# L9741.net
KiCad netlist of a schematic drawn in Altium Designer
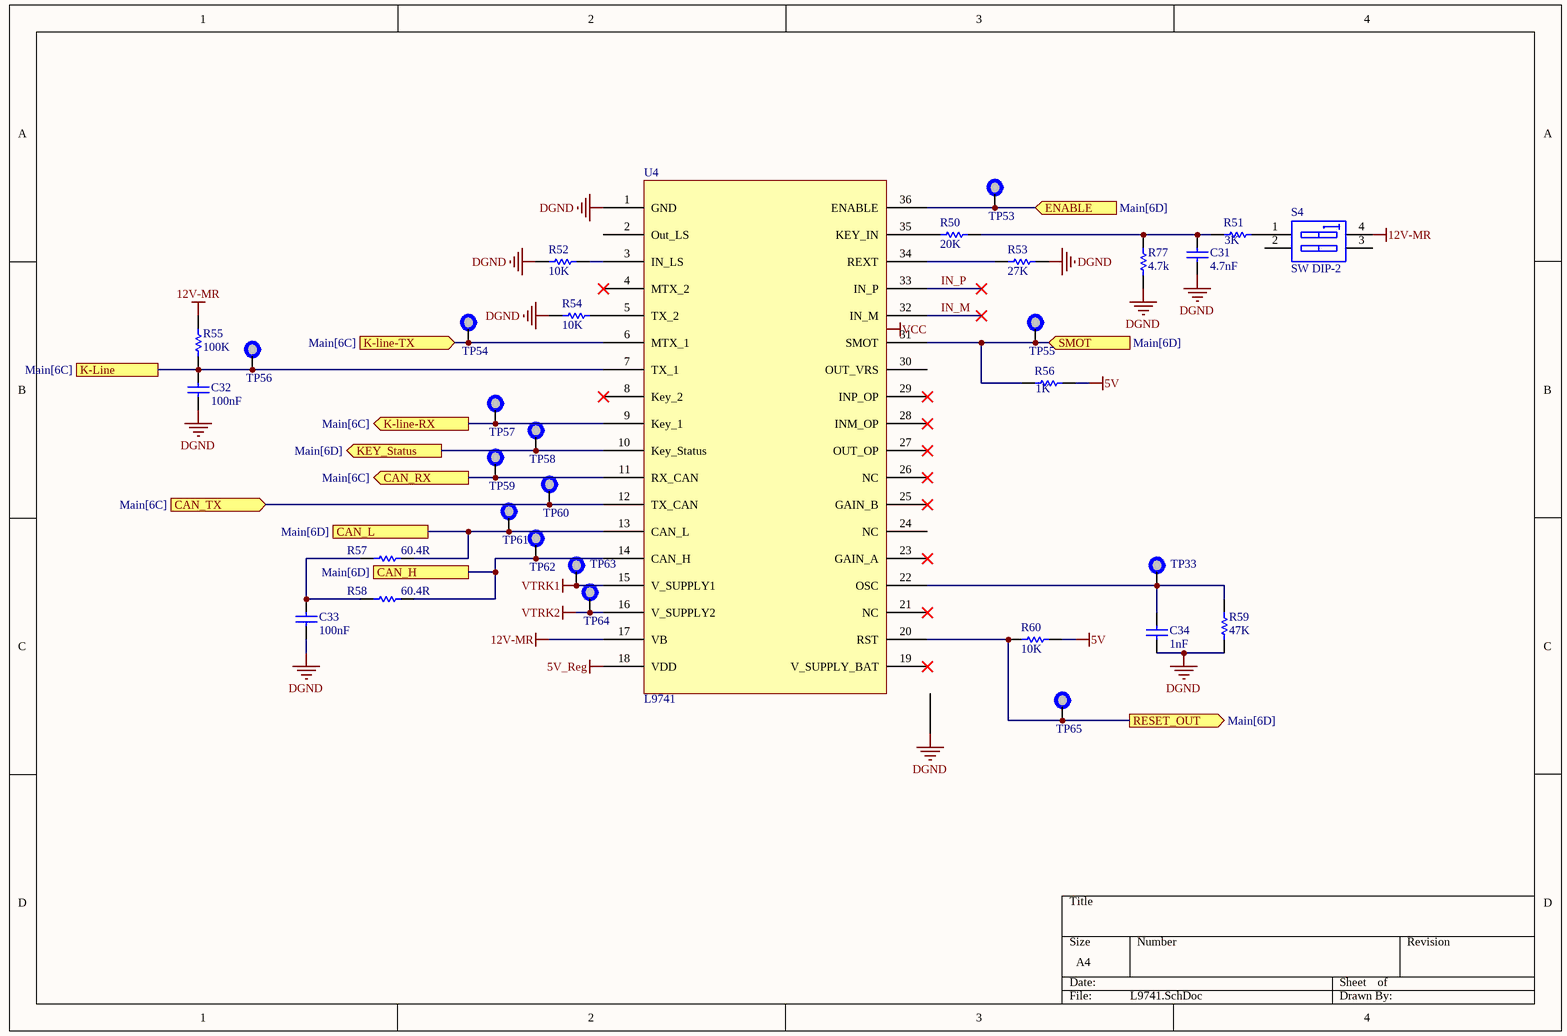
[diagram p0: L9741.SchDoc]

(export (version "E")
  (design (tool "Eeschema 10.0.6"))
  (components
    (comp (ref "C31")
      (value "4.7nF")
      (footprint "0805C")
      (description "LOW ESR")
      (fields (field (name "PUBLISHER") "Altium Limited"))
      (libsource (lib "Miscellaneous Devices") (part "Cap"))
    )
    (comp (ref "C32")
      (value "100nF")
      (footprint "0603c")
      (description "LOW ESR")
      (fields (field (name "PUBLISHER") "Altium Limited"))
      (libsource (lib "Miscellaneous Devices") (part "Cap"))
    )
    (comp (ref "C33")
      (value "100nF")
      (footprint "0603c")
      (description "LOW ESR")
      (fields (field (name "PUBLISHER") "Altium Limited"))
      (libsource (lib "Miscellaneous Devices") (part "Cap"))
    )
    (comp (ref "C34")
      (value "1nF")
      (footprint "0805C")
      (description "LOW ESR")
      (fields (field (name "PUBLISHER") "Altium Limited"))
      (libsource (lib "Miscellaneous Devices") (part "Cap"))
    )
    (comp (ref "R50")
      (value "20K")
      (footprint "0805")
      (description "Resistor")
      (fields (field (name "PUBLISHER") "Altium Limited"))
      (libsource (lib "Miscellaneous Devices") (part "Res1"))
    )
    (comp (ref "R51")
      (value "3K")
      (footprint "0805")
      (description "Resistor")
      (fields (field (name "PUBLISHER") "Altium Limited"))
      (libsource (lib "Miscellaneous Devices") (part "Res1"))
    )
    (comp (ref "R52")
      (value "10K")
      (footprint "0805")
      (description "Resistor")
      (fields (field (name "PUBLISHER") "Altium Limited"))
      (libsource (lib "Miscellaneous Devices") (part "Res1"))
    )
    (comp (ref "R53")
      (value "27K")
      (footprint "0805")
      (description "Resistor")
      (fields (field (name "PUBLISHER") "Altium Limited"))
      (libsource (lib "Miscellaneous Devices") (part "Res1"))
    )
    (comp (ref "R54")
      (value "10K")
      (footprint "0805")
      (description "Resistor")
      (fields (field (name "PUBLISHER") "Altium Limited"))
      (libsource (lib "Miscellaneous Devices") (part "Res1"))
    )
    (comp (ref "R55")
      (value "100K")
      (footprint "0805")
      (description "Resistor")
      (fields (field (name "PUBLISHER") "Altium Limited"))
      (libsource (lib "Miscellaneous Devices") (part "Res1"))
    )
    (comp (ref "R56")
      (value "1K")
      (footprint "0805")
      (description "Resistor")
      (fields (field (name "PUBLISHER") "Altium Limited"))
      (libsource (lib "Miscellaneous Devices") (part "Res1"))
    )
    (comp (ref "R57")
      (value "60.4R")
      (footprint "1206")
      (description "Resistor")
      (fields (field (name "PUBLISHER") "Altium Limited"))
      (libsource (lib "Miscellaneous Devices") (part "Res1"))
    )
    (comp (ref "R58")
      (value "60.4R")
      (footprint "1206")
      (description "Resistor")
      (fields (field (name "PUBLISHER") "Altium Limited"))
      (libsource (lib "Miscellaneous Devices") (part "Res1"))
    )
    (comp (ref "R59")
      (value "47K")
      (footprint "0805")
      (description "Resistor")
      (fields (field (name "PUBLISHER") "Altium Limited"))
      (libsource (lib "Miscellaneous Devices") (part "Res1"))
    )
    (comp (ref "R60")
      (value "10K")
      (footprint "0805")
      (description "Resistor")
      (fields (field (name "PUBLISHER") "Altium Limited"))
      (libsource (lib "Miscellaneous Devices") (part "Res1"))
    )
    (comp (ref "R77")
      (value "4.7k")
      (footprint "0805")
      (description "Resistor")
      (fields (field (name "Comment") "4.7K") (field (name "PUBLISHER") "Altium Limited"))
      (libsource (lib "Miscellaneous Devices") (part "Res1"))
    )
    (comp (ref "S4")
      (value "SW DIP-2")
      (footprint "DIP-4")
      (description "DIP Switch, 2 Position, SPST")
      (fields (field (name "PUBLISHER") "Altium Limited"))
      (libsource (lib "Miscellaneous Devices") (part "SW DIP-2"))
    )
    (comp (ref "TP33") (value "TestPoint") (footprint "TP") (libsource (lib "SchlibV0.1") (part "TestPoint")))
    (comp (ref "TP53") (value "TestPoint") (footprint "TP") (libsource (lib "SchlibV0.1") (part "TestPoint")))
    (comp (ref "TP54") (value "TestPoint") (footprint "TP") (libsource (lib "SchlibV0.1") (part "TestPoint")))
    (comp (ref "TP55") (value "TestPoint") (footprint "TP") (libsource (lib "SchlibV0.1") (part "TestPoint")))
    (comp (ref "TP56") (value "TestPoint") (footprint "TP") (libsource (lib "SchlibV0.1") (part "TestPoint")))
    (comp (ref "TP57") (value "TestPoint") (footprint "TP") (libsource (lib "SchlibV0.1") (part "TestPoint")))
    (comp (ref "TP58") (value "TestPoint") (footprint "TP") (libsource (lib "SchlibV0.1") (part "TestPoint")))
    (comp (ref "TP59") (value "TestPoint") (footprint "TP") (libsource (lib "SchlibV0.1") (part "TestPoint")))
    (comp (ref "TP60") (value "TestPoint") (footprint "TP") (libsource (lib "SchlibV0.1") (part "TestPoint")))
    (comp (ref "TP61") (value "TestPoint") (footprint "TP") (libsource (lib "SchlibV0.1") (part "TestPoint")))
    (comp (ref "TP62") (value "TestPoint") (footprint "TP") (libsource (lib "SchlibV0.1") (part "TestPoint")))
    (comp (ref "TP63") (value "TestPoint") (footprint "TP") (libsource (lib "SchlibV0.1") (part "TestPoint")))
    (comp (ref "TP64") (value "TestPoint") (footprint "TP") (libsource (lib "SchlibV0.1") (part "TestPoint")))
    (comp (ref "TP65") (value "TestPoint") (footprint "TP") (libsource (lib "SchlibV0.1") (part "TestPoint")))
    (comp (ref "U4") (value "L9741") (footprint "L9741") (libsource (lib "SchlibV0.1") (part "L9741")))
  )
  (nets
    (net (code "1") (name "/CAN_H") (class "Default")
      (node (ref "R58") (pin "2") (pinfunction "2_2") (pintype "passive"))
      (node (ref "TP62") (pin "1") (pintype "passive"))
      (node (ref "U4") (pin "14") (pinfunction "CAN_H_14") (pintype "passive"))
    )
    (net (code "2") (name "/CAN_L") (class "Default")
      (node (ref "R57") (pin "2") (pinfunction "2_2") (pintype "passive"))
      (node (ref "TP61") (pin "1") (pintype "passive"))
      (node (ref "U4") (pin "13") (pinfunction "CAN_L_13") (pintype "passive"))
    )
    (net (code "3") (name "/CAN_RX") (class "Default")
      (node (ref "TP59") (pin "1") (pintype "passive"))
      (node (ref "U4") (pin "11") (pinfunction "RX_CAN_11") (pintype "passive"))
    )
    (net (code "4") (name "/CAN_TX") (class "Default")
      (node (ref "TP60") (pin "1") (pintype "passive"))
      (node (ref "U4") (pin "12") (pinfunction "TX_CAN_12") (pintype "passive"))
    )
    (net (code "5") (name "/ENABLE") (class "Default")
      (node (ref "TP53") (pin "1") (pintype "passive"))
      (node (ref "U4") (pin "36") (pinfunction "ENABLE_36") (pintype "passive"))
    )
    (net (code "6") (name "/IN_M") (class "Default")
      (node (ref "U4") (pin "32") (pinfunction "IN_M_32") (pintype "passive+no_connect"))
    )
    (net (code "7") (name "/IN_P") (class "Default")
      (node (ref "U4") (pin "33") (pinfunction "IN_P_33") (pintype "passive+no_connect"))
    )
    (net (code "8") (name "/K-Line") (class "Default")
      (node (ref "C32") (pin "1") (pinfunction "1_1") (pintype "passive"))
      (node (ref "R55") (pin "2") (pinfunction "2_2") (pintype "passive"))
      (node (ref "TP56") (pin "1") (pintype "passive"))
      (node (ref "U4") (pin "7") (pinfunction "TX_1_7") (pintype "passive"))
    )
    (net (code "9") (name "/K-line-RX") (class "Default")
      (node (ref "TP57") (pin "1") (pintype "passive"))
      (node (ref "U4") (pin "9") (pinfunction "Key_1_9") (pintype "passive"))
    )
    (net (code "10") (name "/K-line-TX") (class "Default")
      (node (ref "TP54") (pin "1") (pintype "passive"))
      (node (ref "U4") (pin "6") (pinfunction "MTX_1_6") (pintype "passive"))
    )
    (net (code "11") (name "/KEY_Status") (class "Default")
      (node (ref "TP58") (pin "1") (pintype "passive"))
      (node (ref "U4") (pin "10") (pinfunction "Key_Status_10") (pintype "passive"))
    )
    (net (code "12") (name "/RESET_OUT") (class "Default")
      (node (ref "R60") (pin "2") (pinfunction "2_2") (pintype "passive"))
      (node (ref "TP65") (pin "1") (pintype "passive"))
      (node (ref "U4") (pin "20") (pinfunction "RST_20") (pintype "passive"))
    )
    (net (code "13") (name "/SMOT") (class "Default")
      (node (ref "R56") (pin "1") (pinfunction "1_1") (pintype "passive"))
      (node (ref "TP55") (pin "1") (pintype "passive"))
      (node (ref "U4") (pin "31") (pinfunction "SMOT_31") (pintype "passive"))
    )
    (net (code "14") (name "5V") (class "Default")
      (node (ref "R56") (pin "2") (pinfunction "2_2") (pintype "passive"))
      (node (ref "R60") (pin "1") (pinfunction "1_1") (pintype "passive"))
    )
    (net (code "15") (name "5V_Reg") (class "Default")
      (node (ref "U4") (pin "18") (pinfunction "VDD_18") (pintype "passive"))
    )
    (net (code "16") (name "12V-MR") (class "Default")
      (node (ref "R55") (pin "1") (pinfunction "1_1") (pintype "passive"))
      (node (ref "S4") (pin "4") (pinfunction "B1_4") (pintype "passive"))
      (node (ref "U4") (pin "17") (pinfunction "VB_17") (pintype "passive"))
    )
    (net (code "17") (name "DGND") (class "Default")
      (node (ref "C31") (pin "1") (pinfunction "1_1") (pintype "passive"))
      (node (ref "C32") (pin "2") (pinfunction "2_2") (pintype "passive"))
      (node (ref "C33") (pin "2") (pinfunction "2_2") (pintype "passive"))
      (node (ref "C34") (pin "2") (pinfunction "2_2") (pintype "passive"))
      (node (ref "R52") (pin "2") (pinfunction "2_2") (pintype "passive"))
      (node (ref "R53") (pin "1") (pinfunction "1_1") (pintype "passive"))
      (node (ref "R54") (pin "2") (pinfunction "2_2") (pintype "passive"))
      (node (ref "R59") (pin "2") (pinfunction "2_2") (pintype "passive"))
      (node (ref "R77") (pin "1") (pinfunction "1_1") (pintype "passive"))
      (node (ref "U4") (pin "1") (pinfunction "GND_1") (pintype "passive"))
      (node (ref "U4") (pin "37") (pinfunction "GND_37") (pintype "passive"))
    )
    (net (code "18") (name "Net-(C31-Pad2)") (class "Default")
      (node (ref "C31") (pin "2") (pinfunction "2_2") (pintype "passive"))
      (node (ref "R50") (pin "1") (pinfunction "1_1") (pintype "passive"))
      (node (ref "R51") (pin "1") (pinfunction "1_1") (pintype "passive"))
      (node (ref "R77") (pin "2") (pinfunction "2_2") (pintype "passive"))
    )
    (net (code "19") (name "Net-(C33-Pad1)") (class "Default")
      (node (ref "C33") (pin "1") (pinfunction "1_1") (pintype "passive"))
      (node (ref "R57") (pin "1") (pinfunction "1_1") (pintype "passive"))
      (node (ref "R58") (pin "1") (pinfunction "1_1") (pintype "passive"))
    )
    (net (code "20") (name "Net-(S4-A1)") (class "Default")
      (node (ref "R51") (pin "2") (pinfunction "2_2") (pintype "passive"))
      (node (ref "S4") (pin "1") (pinfunction "A1_1") (pintype "passive"))
    )
    (net (code "21") (name "Net-(U4-IN_LS)") (class "Default")
      (node (ref "R52") (pin "1") (pinfunction "1_1") (pintype "passive"))
      (node (ref "U4") (pin "3") (pinfunction "IN_LS_3") (pintype "passive"))
    )
    (net (code "22") (name "Net-(U4-KEY_IN)") (class "Default")
      (node (ref "R50") (pin "2") (pinfunction "2_2") (pintype "passive"))
      (node (ref "U4") (pin "35") (pinfunction "KEY_IN_35") (pintype "passive"))
    )
    (net (code "23") (name "Net-(U4-OSC)") (class "Default")
      (node (ref "C34") (pin "1") (pinfunction "1_1") (pintype "passive"))
      (node (ref "R59") (pin "1") (pinfunction "1_1") (pintype "passive"))
      (node (ref "TP33") (pin "1") (pintype "passive"))
      (node (ref "U4") (pin "22") (pinfunction "OSC_22") (pintype "passive"))
    )
    (net (code "24") (name "Net-(U4-REXT)") (class "Default")
      (node (ref "R53") (pin "2") (pinfunction "2_2") (pintype "passive"))
      (node (ref "U4") (pin "34") (pinfunction "REXT_34") (pintype "passive"))
    )
    (net (code "25") (name "Net-(U4-TX_2)") (class "Default")
      (node (ref "R54") (pin "1") (pinfunction "1_1") (pintype "passive"))
      (node (ref "U4") (pin "5") (pinfunction "TX_2_5") (pintype "passive"))
    )
    (net (code "27") (name "VTRK1") (class "Default")
      (node (ref "TP63") (pin "1") (pintype "passive"))
      (node (ref "U4") (pin "15") (pinfunction "V_SUPPLY1_15") (pintype "passive"))
    )
    (net (code "28") (name "VTRK2") (class "Default")
      (node (ref "TP64") (pin "1") (pintype "passive"))
      (node (ref "U4") (pin "16") (pinfunction "V_SUPPLY2_16") (pintype "passive"))
    )
    (net (code "29") (name "unconnected-(S4-A2-Pad2)") (class "Default")
      (node (ref "S4") (pin "2") (pinfunction "A2_2") (pintype "passive"))
    )
    (net (code "30") (name "unconnected-(S4-B2-Pad3)") (class "Default")
      (node (ref "S4") (pin "3") (pinfunction "B2_3") (pintype "passive"))
    )
    (net (code "31") (name "unconnected-(U4-GAIN_A-Pad23)") (class "Default")
      (node (ref "U4") (pin "23") (pinfunction "GAIN_A_23") (pintype "passive+no_connect"))
    )
    (net (code "32") (name "unconnected-(U4-GAIN_B-Pad25)") (class "Default")
      (node (ref "U4") (pin "25") (pinfunction "GAIN_B_25") (pintype "passive+no_connect"))
    )
    (net (code "33") (name "unconnected-(U4-INM_OP-Pad28)") (class "Default")
      (node (ref "U4") (pin "28") (pinfunction "INM_OP_28") (pintype "passive+no_connect"))
    )
    (net (code "34") (name "unconnected-(U4-INP_OP-Pad29)") (class "Default")
      (node (ref "U4") (pin "29") (pinfunction "INP_OP_29") (pintype "passive+no_connect"))
    )
    (net (code "35") (name "unconnected-(U4-Key_2-Pad8)") (class "Default")
      (node (ref "U4") (pin "8") (pinfunction "Key_2_8") (pintype "passive+no_connect"))
    )
    (net (code "36") (name "unconnected-(U4-MTX_2-Pad4)") (class "Default")
      (node (ref "U4") (pin "4") (pinfunction "MTX_2_4") (pintype "passive+no_connect"))
    )
    (net (code "37") (name "unconnected-(U4-NC-Pad21)") (class "Default")
      (node (ref "U4") (pin "21") (pinfunction "NC_21") (pintype "passive+no_connect"))
    )
    (net (code "38") (name "unconnected-(U4-NC-Pad24)") (class "Default")
      (node (ref "U4") (pin "24") (pinfunction "NC_24") (pintype "passive"))
    )
    (net (code "39") (name "unconnected-(U4-NC-Pad26)") (class "Default")
      (node (ref "U4") (pin "26") (pinfunction "NC_26") (pintype "passive+no_connect"))
    )
    (net (code "40") (name "unconnected-(U4-OUT_OP-Pad27)") (class "Default")
      (node (ref "U4") (pin "27") (pinfunction "OUT_OP_27") (pintype "passive+no_connect"))
    )
    (net (code "41") (name "unconnected-(U4-OUT_VRS-Pad30)") (class "Default")
      (node (ref "U4") (pin "30") (pinfunction "OUT_VRS_30") (pintype "passive"))
    )
    (net (code "42") (name "unconnected-(U4-Out_LS-Pad2)") (class "Default")
      (node (ref "U4") (pin "2") (pinfunction "Out_LS_2") (pintype "passive"))
    )
    (net (code "43") (name "unconnected-(U4-V_SUPPLY_BAT-Pad19)") (class "Default")
      (node (ref "U4") (pin "19") (pinfunction "V_SUPPLY_BAT_19") (pintype "passive+no_connect"))
    )
  )
)
